# FPGA_AUDIO.net
KiCad netlist of a schematic drawn in Altium Designer
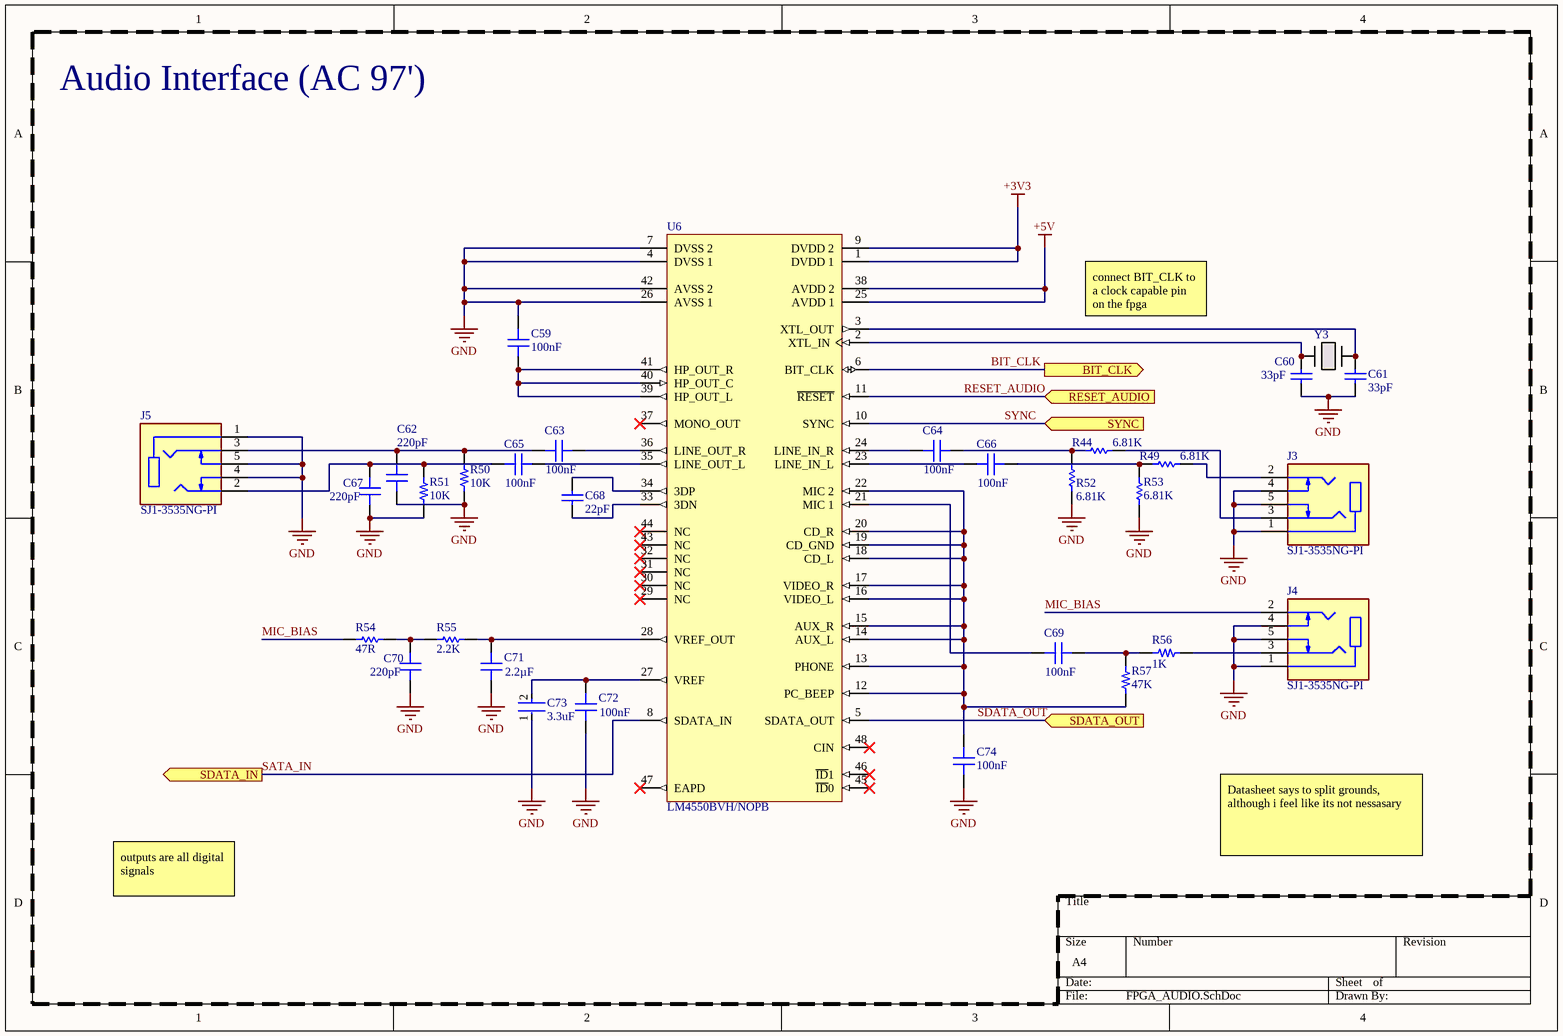
[diagram p0: FPGA_AUDIO.SchDoc]

(export (version "E")
  (design (tool "Eeschema 10.0.6"))
  (components
    (comp (ref "C59")
      (value "CAP CER 0.1UF 100V 10% X7R 0603")
      (footprint "CAP 0603_1608")
      (fields (field (name "CAPACITANCE") "100nF") (field (name "TOLERANCE") "10%"))
      (libsource (lib "Midnight Sun") (part "Capacitor"))
    )
    (comp (ref "C60")
      (value "33pF")
      (footprint "CAPC1005X55X25ML05T10")
      (fields (field (name "PART NUMBER") "GRM1555C1H330JA01D") (field (name "MANUFACTURER") "Murata"))
      (libsource (lib "Altium Content Vault") (part "CAP"))
    )
    (comp (ref "C61")
      (value "33pF")
      (footprint "CAPC1005X55X25ML05T10")
      (fields (field (name "PART NUMBER") "GRM1555C1H330JA01D") (field (name "MANUFACTURER") "Murata"))
      (libsource (lib "Altium Content Vault") (part "CAP"))
    )
    (comp (ref "C62")
      (value "CAP CER 220PF 50V 5% C0G/NP0 0603")
      (footprint "CAP 0603_1608")
      (description "220pF ±5% 50V Ceramic Capacitor C0G, NP0 0603 (1608 Metric)")
      (fields (field (name "CAPACITANCE") "220pF") (field (name "TOLERANCE") "5%"))
      (libsource (lib "Midnight Sun") (part "Capacitor"))
    )
    (comp (ref "C63")
      (value "CAP CER 0.1UF 100V 10% X7R 0603")
      (footprint "CAP 0603_1608")
      (fields (field (name "CAPACITANCE") "100nF") (field (name "TOLERANCE") "10%"))
      (libsource (lib "Midnight Sun") (part "Capacitor"))
    )
    (comp (ref "C64")
      (value "CAP CER 0.1UF 100V 10% X7R 0603")
      (footprint "CAP 0603_1608")
      (fields (field (name "CAPACITANCE") "100nF") (field (name "TOLERANCE") "10%"))
      (libsource (lib "Midnight Sun") (part "Capacitor"))
    )
    (comp (ref "C65")
      (value "CAP CER 0.1UF 100V 10% X7R 0603")
      (footprint "CAP 0603_1608")
      (fields (field (name "CAPACITANCE") "100nF") (field (name "TOLERANCE") "10%"))
      (libsource (lib "Midnight Sun") (part "Capacitor"))
    )
    (comp (ref "C66")
      (value "CAP CER 0.1UF 100V 10% X7R 0603")
      (footprint "CAP 0603_1608")
      (fields (field (name "CAPACITANCE") "100nF") (field (name "TOLERANCE") "10%"))
      (libsource (lib "Midnight Sun") (part "Capacitor"))
    )
    (comp (ref "C67")
      (value "CAP CER 220PF 50V 5% C0G/NP0 0603")
      (footprint "CAP 0603_1608")
      (description "220pF ±5% 50V Ceramic Capacitor C0G, NP0 0603 (1608 Metric)")
      (fields (field (name "CAPACITANCE") "220pF") (field (name "TOLERANCE") "5%"))
      (libsource (lib "Midnight Sun") (part "Capacitor"))
    )
    (comp (ref "C68")
      (value "22pF")
      (footprint "CAPC1005X55X25NL05T10")
      (fields (field (name "PART NUMBER") "GRM1555C1H220JA01D") (field (name "MANUFACTURER") "Murata"))
      (libsource (lib "Altium Content Vault") (part "CAP"))
    )
    (comp (ref "C69")
      (value "CAP CER 0.1UF 100V 10% X7R 0603")
      (footprint "CAP 0603_1608")
      (fields (field (name "CAPACITANCE") "100nF") (field (name "TOLERANCE") "10%"))
      (libsource (lib "Midnight Sun") (part "Capacitor"))
    )
    (comp (ref "C70")
      (value "CAP CER 220PF 50V 5% C0G/NP0 0603")
      (footprint "CAP 0603_1608")
      (description "220pF ±5% 50V Ceramic Capacitor C0G, NP0 0603 (1608 Metric)")
      (fields (field (name "CAPACITANCE") "220pF") (field (name "TOLERANCE") "5%"))
      (libsource (lib "Midnight Sun") (part "Capacitor"))
    )
    (comp (ref "C71")
      (value "CAP CER 2.2UF 25V 10% X5R 0603")
      (footprint "CAP 0603_1608")
      (description "2.2µF ±10% 25V Ceramic Capacitor X5R 0603 (1608 Metric)")
      (fields (field (name "CAPACITANCE") "2.2µF") (field (name "TOLERANCE") "10%"))
      (libsource (lib "Midnight Sun") (part "Capacitor"))
    )
    (comp (ref "C72")
      (value "CAP CER 0.1UF 100V 10% X7R 0603")
      (footprint "CAP 0603_1608")
      (fields (field (name "CAPACITANCE") "100nF") (field (name "TOLERANCE") "10%"))
      (libsource (lib "Midnight Sun") (part "Capacitor"))
    )
    (comp (ref "C73")
      (value "3.3uF")
      (footprint "FP-C1608-080-0_1-IPC_C")
      (description "Multilayer Ceramic Capacitors 3.3μF ±10% 16V X5R SMD 0603")
      (fields (field (name "TOLERANCE") "10%"))
      (libsource (lib "Altium Content Vault") (part "236180d848d6139a670b325ea6854c9"))
    )
    (comp (ref "C74")
      (value "CAP CER 0.1UF 100V 10% X7R 0603")
      (footprint "CAP 0603_1608")
      (fields (field (name "CAPACITANCE") "100nF") (field (name "TOLERANCE") "10%"))
      (libsource (lib "Midnight Sun") (part "Capacitor"))
    )
    (comp (ref "J3")
      (value "SJ1-3535NG-PI")
      (footprint "CUI_SJ1-3535NG-PI")
      (description "3.5 mm Right-Angle Stereo Jack, 5 pin PCB PCB Mount, Isolated Ground, Pink")
      (libsource (lib "BIG_FPGA") (part "SJ1-3535NG-PI"))
    )
    (comp (ref "J4")
      (value "SJ1-3535NG-PI")
      (footprint "CUI_SJ1-3535NG-PI")
      (description "3.5 mm Right-Angle Stereo Jack, 5 pin PCB PCB Mount, Isolated Ground, Pink")
      (libsource (lib "BIG_FPGA") (part "SJ1-3535NG-PI"))
    )
    (comp (ref "J5")
      (value "SJ1-3535NG-PI")
      (footprint "CUI_SJ1-3535NG-PI")
      (description "3.5 mm Right-Angle Stereo Jack, 5 pin PCB PCB Mount, Isolated Ground, Pink")
      (libsource (lib "") (part "SJ1-3535NG-PI_1"))
    )
    (comp (ref "R44")
      (value "6.81K")
      (footprint "RESC1005X40X25ML05T05")
      (fields (field (name "PART NUMBER") "ERJ-2RKF6811X") (field (name "MANUFACTURER") "Panasonic"))
      (libsource (lib "Altium Content Vault") (part "RES"))
    )
    (comp (ref "R49")
      (value "6.81K")
      (footprint "RESC1005X40X25ML05T05")
      (fields (field (name "PART NUMBER") "ERJ-2RKF6811X") (field (name "MANUFACTURER") "Panasonic"))
      (libsource (lib "Altium Content Vault") (part "RES"))
    )
    (comp (ref "R50")
      (value "10K")
      (footprint "RES 0603_1608")
      (description "10 ±1% 0.1W, 1/10W Chip Resistor 0603 (1608 Metric) Automotive AEC-Q200 Thick Film")
      (libsource (lib "Midnight Sun") (part "Resistor"))
    )
    (comp (ref "R51")
      (value "10K")
      (footprint "RES 0603_1608")
      (description "10 ±1% 0.1W, 1/10W Chip Resistor 0603 (1608 Metric) Automotive AEC-Q200 Thick Film")
      (libsource (lib "Midnight Sun") (part "Resistor"))
    )
    (comp (ref "R52")
      (value "6.81K")
      (footprint "RESC1005X40X25ML05T05")
      (fields (field (name "PART NUMBER") "ERJ-2RKF6811X") (field (name "MANUFACTURER") "Panasonic"))
      (libsource (lib "Altium Content Vault") (part "RES"))
    )
    (comp (ref "R53")
      (value "6.81K")
      (footprint "RESC1005X40X25ML05T05")
      (fields (field (name "PART NUMBER") "ERJ-2RKF6811X") (field (name "MANUFACTURER") "Panasonic"))
      (libsource (lib "Altium Content Vault") (part "RES"))
    )
    (comp (ref "R54")
      (value "47R")
      (footprint "RESC1608X55X30NL15T15")
      (description "Chip Resistor, 47 Ohm, +/- 1%, 0.1 W, -55 to 155 degC, 0603 (1608 Metric), RoHS, Tape and Reel")
      (fields (field (name "TOLERANCE") "1%"))
      (libsource (lib "Altium Content Vault") (part "RES-2"))
    )
    (comp (ref "R55")
      (value "2.2K")
      (footprint "RESC1608X55X25LL10T15")
      (fields (field (name "PART NUMBER") "RC0603FR-132K2L") (field (name "MANUFACTURER") "Yageo"))
      (libsource (lib "Altium Content Vault") (part "RES"))
    )
    (comp (ref "R56")
      (value "1K")
      (footprint "RES 0603_1608")
      (description "1 kOhms ±1% 0.1W, 1/10W Chip Resistor 0603 (1608 Metric) Moisture Resistant Thick Film")
      (libsource (lib "Midnight Sun") (part "Resistor"))
    )
    (comp (ref "R57")
      (value "47K")
      (footprint "RES 0603_1608")
      (libsource (lib "Midnight Sun") (part "Resistor"))
    )
    (comp (ref "U6")
      (value "LM4550BVH/NOPB")
      (footprint "PT0048A_L")
      (description "AC '97 Rev 2.1 Codec with Sample Rate Conversion and National 3D Sound, 48-pin LQFP, Pb-Free")
      (fields (field (name "MANUFACTURER") "Texas Instruments"))
      (libsource (lib "Altium Content Vault") (part "AUD-SPA-LM4550-48"))
    )
    (comp (ref "Y3")
      (value "FOXSDLF245F-20")
      (footprint "CRYSTAL_HC49SDLF_FXT")
      (description "No Description Available")
      (libsource (lib "BIG_FPGA") (part "FOXSDLF245F-20"))
    )
  )
  (nets
    (net (code "1") (name "+3V3") (class "Default")
      (node (ref "U6") (pin "1") (pinfunction "DVDD_1_1") (pintype "power_in"))
      (node (ref "U6") (pin "9") (pinfunction "DVDD_2_9") (pintype "power_in"))
    )
    (net (code "2") (name "+5V") (class "Default")
      (node (ref "U6") (pin "25") (pinfunction "AVDD_1_25") (pintype "power_in"))
      (node (ref "U6") (pin "38") (pinfunction "AVDD_2_38") (pintype "power_in"))
    )
    (net (code "3") (name "/BIT_CLK") (class "Default")
      (node (ref "U6") (pin "6") (pinfunction "BIT_CLK_6") (pintype "bidirectional"))
    )
    (net (code "4") (name "/MIC_BIAS") (class "Default")
      (node (ref "J4") (pin "2") (pinfunction "2_2") (pintype "passive"))
      (node (ref "R54") (pin "1") (pinfunction "1_1") (pintype "passive"))
    )
    (net (code "5") (name "/RESET_AUDIO") (class "Default")
      (node (ref "U6") (pin "11") (pinfunction "~{RESET}_11") (pintype "input"))
    )
    (net (code "6") (name "/SATA_IN") (class "Default")
      (node (ref "U6") (pin "8") (pinfunction "SDATA_IN_8") (pintype "output"))
    )
    (net (code "7") (name "/SDATA_OUT") (class "Default")
      (node (ref "U6") (pin "5") (pinfunction "SDATA_OUT_5") (pintype "input"))
    )
    (net (code "8") (name "/SYNC") (class "Default")
      (node (ref "U6") (pin "10") (pinfunction "SYNC_10") (pintype "input"))
    )
    (net (code "9") (name "GND") (class "Default")
      (node (ref "C59") (pin "1") (pinfunction "1_1") (pintype "passive"))
      (node (ref "C60") (pin "2") (pinfunction "2_2") (pintype "passive"))
      (node (ref "C61") (pin "2") (pinfunction "2_2") (pintype "passive"))
      (node (ref "C62") (pin "2") (pinfunction "2_2") (pintype "passive"))
      (node (ref "C67") (pin "2") (pinfunction "2_2") (pintype "passive"))
      (node (ref "C70") (pin "2") (pinfunction "2_2") (pintype "passive"))
      (node (ref "C71") (pin "2") (pinfunction "2_2") (pintype "passive"))
      (node (ref "C72") (pin "2") (pinfunction "2_2") (pintype "passive"))
      (node (ref "C73") (pin "1") (pinfunction "1_1") (pintype "passive"))
      (node (ref "C74") (pin "2") (pinfunction "2_2") (pintype "passive"))
      (node (ref "J3") (pin "1") (pinfunction "1_1") (pintype "passive"))
      (node (ref "J3") (pin "4") (pinfunction "4_4") (pintype "passive"))
      (node (ref "J3") (pin "5") (pinfunction "5_5") (pintype "passive"))
      (node (ref "J4") (pin "1") (pinfunction "1_1") (pintype "passive"))
      (node (ref "J4") (pin "4") (pinfunction "4_4") (pintype "passive"))
      (node (ref "J4") (pin "5") (pinfunction "5_5") (pintype "passive"))
      (node (ref "J5") (pin "1") (pinfunction "1_1") (pintype "passive"))
      (node (ref "J5") (pin "4") (pinfunction "4_4") (pintype "passive"))
      (node (ref "J5") (pin "5") (pinfunction "5_5") (pintype "passive"))
      (node (ref "R50") (pin "2") (pinfunction "2_2") (pintype "passive"))
      (node (ref "R51") (pin "2") (pinfunction "2_2") (pintype "passive"))
      (node (ref "R52") (pin "1") (pinfunction "1_1") (pintype "passive"))
      (node (ref "R53") (pin "1") (pinfunction "1_1") (pintype "passive"))
      (node (ref "U6") (pin "26") (pinfunction "AVSS_1_26") (pintype "power_in"))
      (node (ref "U6") (pin "4") (pinfunction "DVSS_1_4") (pintype "power_in"))
      (node (ref "U6") (pin "42") (pinfunction "AVSS_2_42") (pintype "power_in"))
      (node (ref "U6") (pin "7") (pinfunction "DVSS_2_7") (pintype "power_in"))
    )
    (net (code "10") (name "Net-(C62-Pad1)") (class "Default")
      (node (ref "C62") (pin "1") (pinfunction "1_1") (pintype "passive"))
      (node (ref "C63") (pin "1") (pinfunction "1_1") (pintype "passive"))
      (node (ref "J5") (pin "3") (pinfunction "3_3") (pintype "passive"))
      (node (ref "R50") (pin "1") (pinfunction "1_1") (pintype "passive"))
    )
    (net (code "11") (name "Net-(C64-Pad2)") (class "Default")
      (node (ref "C64") (pin "2") (pinfunction "2_2") (pintype "passive"))
      (node (ref "R44") (pin "1") (pinfunction "1_1") (pintype "passive"))
      (node (ref "R52") (pin "2") (pinfunction "2_2") (pintype "passive"))
    )
    (net (code "12") (name "Net-(C65-Pad1)") (class "Default")
      (node (ref "C65") (pin "1") (pinfunction "1_1") (pintype "passive"))
      (node (ref "C67") (pin "1") (pinfunction "1_1") (pintype "passive"))
      (node (ref "J5") (pin "2") (pinfunction "2_2") (pintype "passive"))
      (node (ref "R51") (pin "1") (pinfunction "1_1") (pintype "passive"))
    )
    (net (code "13") (name "Net-(C66-Pad2)") (class "Default")
      (node (ref "C66") (pin "2") (pinfunction "2_2") (pintype "passive"))
      (node (ref "R49") (pin "1") (pinfunction "1_1") (pintype "passive"))
      (node (ref "R53") (pin "2") (pinfunction "2_2") (pintype "passive"))
    )
    (net (code "14") (name "Net-(C69-Pad2)") (class "Default")
      (node (ref "C69") (pin "2") (pinfunction "2_2") (pintype "passive"))
      (node (ref "R56") (pin "1") (pinfunction "1_1") (pintype "passive"))
      (node (ref "R57") (pin "1") (pinfunction "1_1") (pintype "passive"))
    )
    (net (code "15") (name "Net-(C70-Pad1)") (class "Default")
      (node (ref "C70") (pin "1") (pinfunction "1_1") (pintype "passive"))
      (node (ref "R54") (pin "2") (pinfunction "2_2") (pintype "passive"))
      (node (ref "R55") (pin "1") (pinfunction "1_1") (pintype "passive"))
    )
    (net (code "16") (name "Net-(J3-Pad2)") (class "Default")
      (node (ref "J3") (pin "2") (pinfunction "2_2") (pintype "passive"))
      (node (ref "R49") (pin "2") (pinfunction "2_2") (pintype "passive"))
    )
    (net (code "17") (name "Net-(J3-Pad3)") (class "Default")
      (node (ref "J3") (pin "3") (pinfunction "3_3") (pintype "passive"))
      (node (ref "R44") (pin "2") (pinfunction "2_2") (pintype "passive"))
    )
    (net (code "18") (name "Net-(J4-Pad3)") (class "Default")
      (node (ref "J4") (pin "3") (pinfunction "3_3") (pintype "passive"))
      (node (ref "R56") (pin "2") (pinfunction "2_2") (pintype "passive"))
    )
    (net (code "19") (name "Net-(U6-3DN)") (class "Default")
      (node (ref "C68") (pin "2") (pinfunction "2_2") (pintype "passive"))
      (node (ref "U6") (pin "33") (pinfunction "3DN_33") (pintype "output"))
    )
    (net (code "20") (name "Net-(U6-3DP)") (class "Default")
      (node (ref "C68") (pin "1") (pinfunction "1_1") (pintype "passive"))
      (node (ref "U6") (pin "34") (pinfunction "3DP_34") (pintype "output"))
    )
    (net (code "21") (name "Net-(U6-AUX_L)") (class "Default")
      (node (ref "C74") (pin "1") (pinfunction "1_1") (pintype "passive"))
      (node (ref "R57") (pin "2") (pinfunction "2_2") (pintype "passive"))
      (node (ref "U6") (pin "12") (pinfunction "PC_BEEP_12") (pintype "input"))
      (node (ref "U6") (pin "13") (pinfunction "PHONE_13") (pintype "input"))
      (node (ref "U6") (pin "14") (pinfunction "AUX_L_14") (pintype "input"))
      (node (ref "U6") (pin "15") (pinfunction "AUX_R_15") (pintype "input"))
      (node (ref "U6") (pin "16") (pinfunction "VIDEO_L_16") (pintype "input"))
      (node (ref "U6") (pin "17") (pinfunction "VIDEO_R_17") (pintype "input"))
      (node (ref "U6") (pin "18") (pinfunction "CD_L_18") (pintype "input"))
      (node (ref "U6") (pin "19") (pinfunction "CD_GND_19") (pintype "input"))
      (node (ref "U6") (pin "20") (pinfunction "CD_R_20") (pintype "input"))
      (node (ref "U6") (pin "22") (pinfunction "MIC_2_22") (pintype "input"))
    )
    (net (code "22") (name "Net-(U6-HP_OUT_C)") (class "Default")
      (node (ref "C59") (pin "2") (pinfunction "2_2") (pintype "passive"))
      (node (ref "U6") (pin "39") (pinfunction "HP_OUT_L_39") (pintype "output"))
      (node (ref "U6") (pin "40") (pinfunction "HP_OUT_C_40") (pintype "input"))
      (node (ref "U6") (pin "41") (pinfunction "HP_OUT_R_41") (pintype "output"))
    )
    (net (code "23") (name "Net-(U6-LINE_IN_L)") (class "Default")
      (node (ref "C66") (pin "1") (pinfunction "1_1") (pintype "passive"))
      (node (ref "U6") (pin "23") (pinfunction "LINE_IN_L_23") (pintype "input"))
    )
    (net (code "24") (name "Net-(U6-LINE_IN_R)") (class "Default")
      (node (ref "C64") (pin "1") (pinfunction "1_1") (pintype "passive"))
      (node (ref "U6") (pin "24") (pinfunction "LINE_IN_R_24") (pintype "input"))
    )
    (net (code "25") (name "Net-(U6-LINE_OUT_L)") (class "Default")
      (node (ref "C65") (pin "2") (pinfunction "2_2") (pintype "passive"))
      (node (ref "U6") (pin "35") (pinfunction "LINE_OUT_L_35") (pintype "output"))
    )
    (net (code "26") (name "Net-(U6-LINE_OUT_R)") (class "Default")
      (node (ref "C63") (pin "2") (pinfunction "2_2") (pintype "passive"))
      (node (ref "U6") (pin "36") (pinfunction "LINE_OUT_R_36") (pintype "output"))
    )
    (net (code "27") (name "Net-(U6-MIC_1)") (class "Default")
      (node (ref "C69") (pin "1") (pinfunction "1_1") (pintype "passive"))
      (node (ref "U6") (pin "21") (pinfunction "MIC_1_21") (pintype "input"))
    )
    (net (code "28") (name "Net-(U6-VREF)") (class "Default")
      (node (ref "C72") (pin "1") (pinfunction "1_1") (pintype "passive"))
      (node (ref "C73") (pin "2") (pinfunction "2_2") (pintype "passive"))
      (node (ref "U6") (pin "27") (pinfunction "VREF_27") (pintype "output"))
    )
    (net (code "29") (name "Net-(U6-VREF_OUT)") (class "Default")
      (node (ref "C71") (pin "1") (pinfunction "1_1") (pintype "passive"))
      (node (ref "R55") (pin "2") (pinfunction "2_2") (pintype "passive"))
      (node (ref "U6") (pin "28") (pinfunction "VREF_OUT_28") (pintype "output"))
    )
    (net (code "30") (name "Net-(U6-XTL_IN)") (class "Default")
      (node (ref "C60") (pin "1") (pinfunction "1_1") (pintype "passive"))
      (node (ref "U6") (pin "2") (pinfunction "XTL_IN_2") (pintype "input"))
      (node (ref "Y3") (pin "2") (pinfunction "2_2") (pintype "passive"))
    )
    (net (code "31") (name "Net-(U6-XTL_OUT)") (class "Default")
      (node (ref "C61") (pin "1") (pinfunction "1_1") (pintype "passive"))
      (node (ref "U6") (pin "3") (pinfunction "XTL_OUT_3") (pintype "output"))
      (node (ref "Y3") (pin "1") (pinfunction "1_1") (pintype "passive"))
    )
    (net (code "32") (name "unconnected-(U6-CIN-Pad48)") (class "Default")
      (node (ref "U6") (pin "48") (pinfunction "CIN_48") (pintype "input+no_connect"))
    )
    (net (code "33") (name "unconnected-(U6-EAPD-Pad47)") (class "Default")
      (node (ref "U6") (pin "47") (pinfunction "EAPD_47") (pintype "output+no_connect"))
    )
    (net (code "34") (name "unconnected-(U6-MONO_OUT-Pad37)") (class "Default")
      (node (ref "U6") (pin "37") (pinfunction "MONO_OUT_37") (pintype "output+no_connect"))
    )
    (net (code "35") (name "unconnected-(U6-NC-Pad29)") (class "Default")
      (node (ref "U6") (pin "29") (pinfunction "NC_29") (pintype "passive+no_connect"))
    )
    (net (code "36") (name "unconnected-(U6-NC-Pad30)") (class "Default")
      (node (ref "U6") (pin "30") (pinfunction "NC_30") (pintype "passive+no_connect"))
    )
    (net (code "37") (name "unconnected-(U6-NC-Pad31)") (class "Default")
      (node (ref "U6") (pin "31") (pinfunction "NC_31") (pintype "passive+no_connect"))
    )
    (net (code "38") (name "unconnected-(U6-NC-Pad32)") (class "Default")
      (node (ref "U6") (pin "32") (pinfunction "NC_32") (pintype "passive+no_connect"))
    )
    (net (code "39") (name "unconnected-(U6-NC-Pad43)") (class "Default")
      (node (ref "U6") (pin "43") (pinfunction "NC_43") (pintype "passive+no_connect"))
    )
    (net (code "40") (name "unconnected-(U6-NC-Pad44)") (class "Default")
      (node (ref "U6") (pin "44") (pinfunction "NC_44") (pintype "passive+no_connect"))
    )
    (net (code "41") (name "unconnected-(U6-~{ID}0-Pad45)") (class "Default")
      (node (ref "U6") (pin "45") (pinfunction "~{ID}0_45") (pintype "input+no_connect"))
    )
    (net (code "42") (name "unconnected-(U6-~{ID}1-Pad46)") (class "Default")
      (node (ref "U6") (pin "46") (pinfunction "~{ID}1_46") (pintype "input+no_connect"))
    )
  )
)
